# AeroQuad_v300.net
KiCad netlist of a schematic drawn in EAGLE
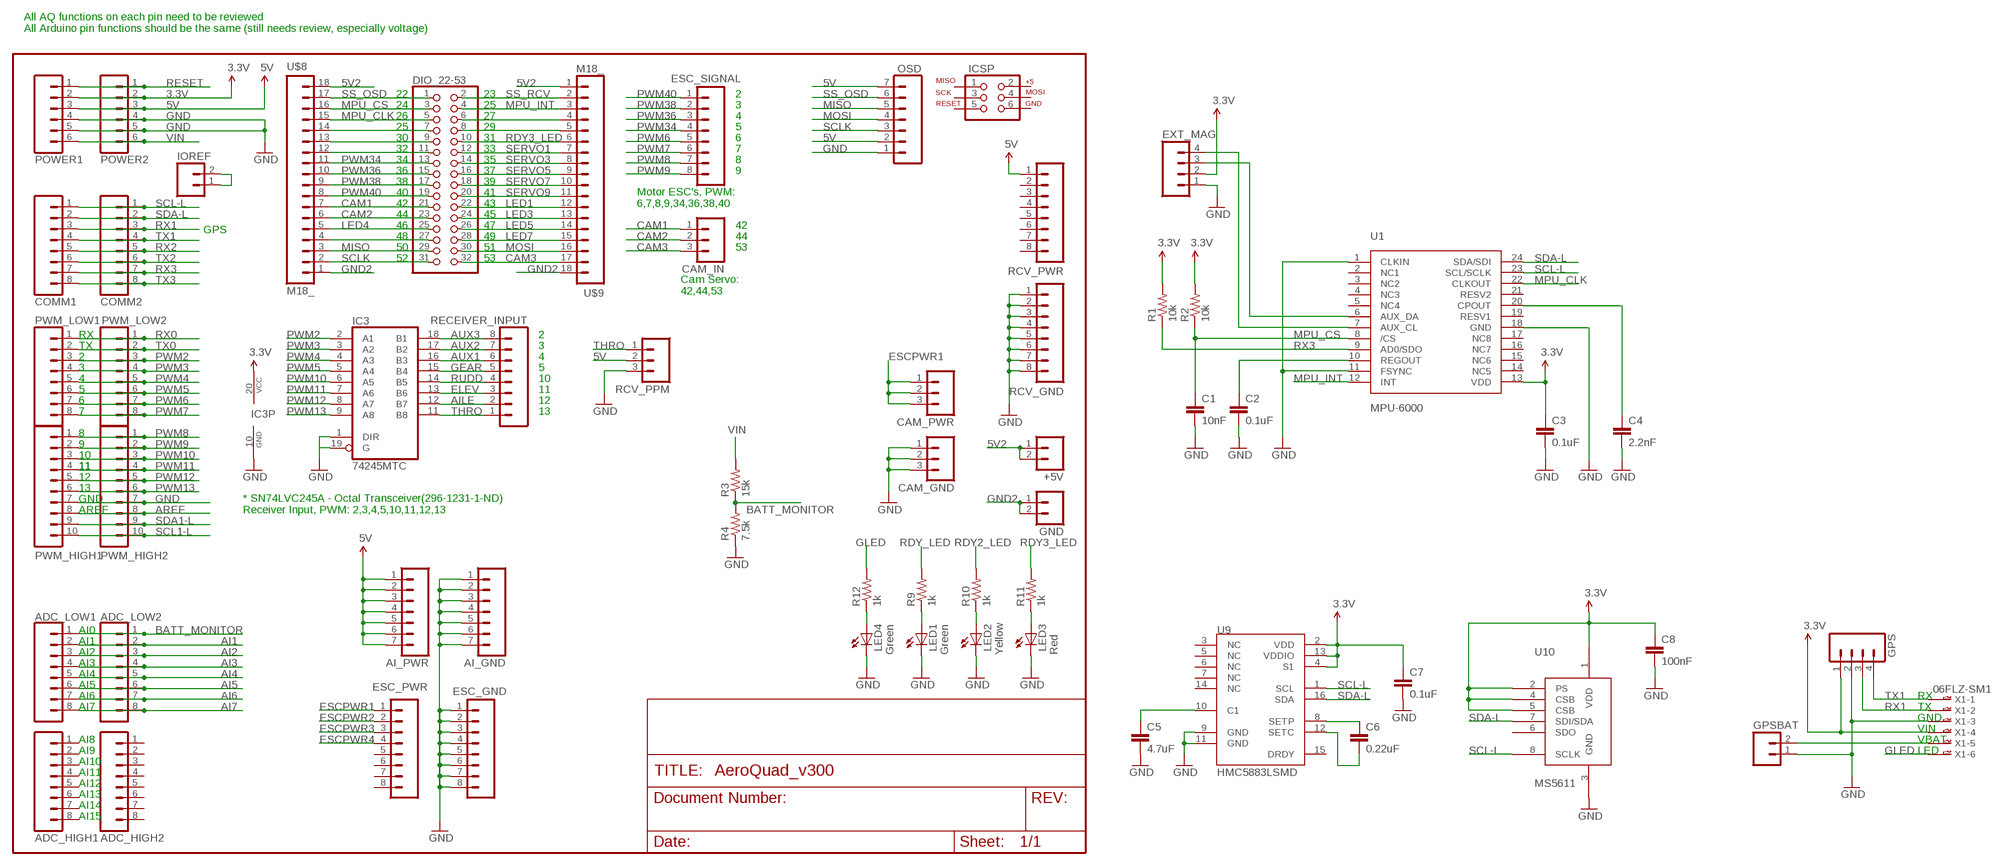
[diagram p0: schematic, sheet 1]

(export (version "E")
  (design (tool "Eeschema 10.0.6"))
  (components
    (comp (ref "+5V")
      (value "M02PTH")
      (footprint "eagle-import:1X02")
      (libsource (lib "eagle-import") (part "M02PTH"))
    )
    (comp (ref "ADC_HIGH1")
      (value "M08LOCK")
      (footprint "eagle-import:1X08_LOCK")
      (libsource (lib "eagle-import") (part "M08LOCK"))
    )
    (comp (ref "ADC_HIGH2")
      (value "M08LOCK")
      (footprint "eagle-import:1X08_LOCK")
      (libsource (lib "eagle-import") (part "M08LOCK"))
    )
    (comp (ref "ADC_LOW1")
      (value "M08LOCK")
      (footprint "eagle-import:1X08_LOCK")
      (libsource (lib "eagle-import") (part "M08LOCK"))
    )
    (comp (ref "ADC_LOW2")
      (value "M08LOCK")
      (footprint "eagle-import:1X08_LOCK")
      (libsource (lib "eagle-import") (part "M08LOCK"))
    )
    (comp (ref "AI_GND")
      (value "M07")
      (footprint "eagle-import:1X07")
      (libsource (lib "eagle-import") (part "M07"))
    )
    (comp (ref "AI_PWR")
      (value "M07")
      (footprint "eagle-import:1X07")
      (libsource (lib "eagle-import") (part "M07"))
    )
    (comp (ref "C1")
      (value "10nF")
      (footprint "eagle-import:0402-CAP")
      (libsource (lib "eagle-import") (part "CAP0402-CAP"))
    )
    (comp (ref "C2")
      (value "0.1uF")
      (footprint "eagle-import:0402-CAP")
      (libsource (lib "eagle-import") (part "CAP0402-CAP"))
    )
    (comp (ref "C3")
      (value "0.1uF")
      (footprint "eagle-import:0402-CAP")
      (libsource (lib "eagle-import") (part "CAP0402-CAP"))
    )
    (comp (ref "C4")
      (value "2.2nF")
      (footprint "eagle-import:0402-CAP")
      (libsource (lib "eagle-import") (part "CAP0402-CAP"))
    )
    (comp (ref "C5")
      (value "4.7uF")
      (footprint "eagle-import:0402-CAP")
      (libsource (lib "eagle-import") (part "CAP0402-CAP"))
    )
    (comp (ref "C6")
      (value "0.22uF")
      (footprint "eagle-import:0402-CAP")
      (libsource (lib "eagle-import") (part "CAP0402-CAP"))
    )
    (comp (ref "C7")
      (value "0.1uF")
      (footprint "eagle-import:0402-CAP")
      (libsource (lib "eagle-import") (part "CAP0402-CAP"))
    )
    (comp (ref "C8")
      (value "100nF")
      (footprint "eagle-import:0402-CAP")
      (libsource (lib "eagle-import") (part "CAP0402-CAP"))
    )
    (comp (ref "CAM_GND")
      (value "M03LOCK")
      (footprint "eagle-import:1X03_LOCK")
      (libsource (lib "eagle-import") (part "M03LOCK"))
    )
    (comp (ref "CAM_IN")
      (value "M03LOCK")
      (footprint "eagle-import:1X03_LOCK")
      (libsource (lib "eagle-import") (part "M03LOCK"))
    )
    (comp (ref "CAM_PWR")
      (value "M03LOCK")
      (footprint "eagle-import:1X03_LOCK")
      (libsource (lib "eagle-import") (part "M03LOCK"))
    )
    (comp (ref "COMM1")
      (value "M08LOCK")
      (footprint "eagle-import:1X08_LOCK")
      (libsource (lib "eagle-import") (part "M08LOCK"))
    )
    (comp (ref "COMM2")
      (value "M08LOCK")
      (footprint "eagle-import:1X08_LOCK")
      (libsource (lib "eagle-import") (part "M08LOCK"))
    )
    (comp (ref "DIO_22-53")
      (value "PINHD-2X16")
      (footprint "eagle-import:2X16")
      (libsource (lib "eagle-import") (part "PINHD-2X16"))
    )
    (comp (ref "ESC_GND")
      (value "M11LOCK")
      (footprint "eagle-import:1X08_LOCK")
      (libsource (lib "eagle-import") (part "M08LOCK"))
    )
    (comp (ref "ESC_PWR")
      (value "M11LOCK")
      (footprint "eagle-import:1X08_LOCK")
      (libsource (lib "eagle-import") (part "M08LOCK"))
    )
    (comp (ref "ESC_SIGNAL")
      (value "M11LOCK")
      (footprint "eagle-import:1X08_LOCK")
      (libsource (lib "eagle-import") (part "M08LOCK"))
    )
    (comp (ref "EXT_MAG")
      (value "M04LOCK")
      (footprint "eagle-import:1X04_LOCK")
      (libsource (lib "eagle-import") (part "M04LOCK"))
    )
    (comp (ref "GND")
      (value "M02PTH")
      (footprint "eagle-import:1X02")
      (libsource (lib "eagle-import") (part "M02PTH"))
    )
    (comp (ref "GPS")
      (value "M04LOCK")
      (footprint "eagle-import:1X04_LOCK")
      (libsource (lib "eagle-import") (part "M04LOCK"))
    )
    (comp (ref "GPSBAT")
      (value "M02PTH")
      (footprint "eagle-import:1X02")
      (libsource (lib "eagle-import") (part "M02PTH"))
    )
    (comp (ref "IC3")
      (value "74245MTC")
      (footprint "eagle-import:SSOP20")
      (libsource (lib "eagle-import") (part "74245MTC"))
    )
    (comp (ref "ICSP")
      (value "AVR_SPI_PRG_6NS")
      (footprint "eagle-import:2X3-NS")
      (libsource (lib "eagle-import") (part "AVR_SPI_PRG_6NS"))
    )
    (comp (ref "IOREF")
      (value "M02LOCK")
      (footprint "eagle-import:1X02_LOCK")
      (libsource (lib "eagle-import") (part "M02LOCK"))
    )
    (comp (ref "LED1")
      (value "Green")
      (footprint "eagle-import:LED-0603")
      (libsource (lib "eagle-import") (part "LED0603"))
    )
    (comp (ref "LED2")
      (value "Yellow")
      (footprint "eagle-import:LED-0603")
      (libsource (lib "eagle-import") (part "LED0603"))
    )
    (comp (ref "LED3")
      (value "Red")
      (footprint "eagle-import:LED-0603")
      (libsource (lib "eagle-import") (part "LED0603"))
    )
    (comp (ref "LED4")
      (value "Green")
      (footprint "eagle-import:LED-0603")
      (libsource (lib "eagle-import") (part "LED0603"))
    )
    (comp (ref "OSD")
      (value "M07LOCK")
      (footprint "eagle-import:1X07_LOCK")
      (libsource (lib "eagle-import") (part "M07LOCK"))
    )
    (comp (ref "POWER1")
      (value "M06LOCK")
      (footprint "eagle-import:1X06_LOCK")
      (libsource (lib "eagle-import") (part "M06LOCK"))
    )
    (comp (ref "POWER2")
      (value "M06LOCK")
      (footprint "eagle-import:1X06_LOCK")
      (libsource (lib "eagle-import") (part "M06LOCK"))
    )
    (comp (ref "PWM_HIGH1")
      (value "M10LOCK")
      (footprint "eagle-import:1X10_LOCK")
      (libsource (lib "eagle-import") (part "M10LOCK"))
    )
    (comp (ref "PWM_HIGH2")
      (value "M10LOCK")
      (footprint "eagle-import:1X10_LOCK")
      (libsource (lib "eagle-import") (part "M10LOCK"))
    )
    (comp (ref "PWM_LOW1")
      (value "M08LOCK")
      (footprint "eagle-import:1X08_LOCK")
      (libsource (lib "eagle-import") (part "M08LOCK"))
    )
    (comp (ref "PWM_LOW2")
      (value "M08LOCK")
      (footprint "eagle-import:1X08_LOCK")
      (libsource (lib "eagle-import") (part "M08LOCK"))
    )
    (comp (ref "R1")
      (value "10k")
      (footprint "eagle-import:0402-RES")
      (libsource (lib "eagle-import") (part "RESISTOR0402-RES"))
    )
    (comp (ref "R2")
      (value "10k")
      (footprint "eagle-import:0402-RES")
      (libsource (lib "eagle-import") (part "RESISTOR0402-RES"))
    )
    (comp (ref "R3")
      (value "15k")
      (footprint "eagle-import:0402-RES")
      (libsource (lib "eagle-import") (part "RESISTOR0402-RES"))
    )
    (comp (ref "R4")
      (value "7.5k")
      (footprint "eagle-import:0402-RES")
      (libsource (lib "eagle-import") (part "RESISTOR0402-RES"))
    )
    (comp (ref "R9")
      (value "1k")
      (footprint "eagle-import:0402-RES")
      (libsource (lib "eagle-import") (part "RESISTOR0402-RES"))
    )
    (comp (ref "R10")
      (value "1k")
      (footprint "eagle-import:0402-RES")
      (libsource (lib "eagle-import") (part "RESISTOR0402-RES"))
    )
    (comp (ref "R11")
      (value "1k")
      (footprint "eagle-import:0402-RES")
      (libsource (lib "eagle-import") (part "RESISTOR0402-RES"))
    )
    (comp (ref "R12")
      (value "1k")
      (footprint "eagle-import:0402-RES")
      (libsource (lib "eagle-import") (part "RESISTOR0402-RES"))
    )
    (comp (ref "RCV_GND")
      (value "M10LOCK")
      (footprint "eagle-import:1X08_LOCK")
      (libsource (lib "eagle-import") (part "M08LOCK"))
    )
    (comp (ref "RCV_PPM")
      (value "M03LOCK")
      (footprint "eagle-import:1X03_LOCK")
      (libsource (lib "eagle-import") (part "M03LOCK"))
    )
    (comp (ref "RCV_PWR")
      (value "M10LOCK")
      (footprint "eagle-import:1X08_LOCK")
      (libsource (lib "eagle-import") (part "M08LOCK"))
    )
    (comp (ref "RECEIVER_INPUT")
      (value "M08LOCK")
      (footprint "eagle-import:1X08_LOCK")
      (libsource (lib "eagle-import") (part "M08LOCK"))
    )
    (comp (ref "U$8")
      (value "M18_")
      (footprint "eagle-import:1X18")
      (libsource (lib "eagle-import") (part "M18_"))
    )
    (comp (ref "U$9")
      (value "M18_")
      (footprint "eagle-import:1X18")
      (libsource (lib "eagle-import") (part "M18_"))
    )
    (comp (ref "U1")
      (value "MPU-6000")
      (footprint "eagle-import:QFN-24")
      (libsource (lib "eagle-import") (part "MPU-6000"))
    )
    (comp (ref "U9")
      (value "HMC5883LSMD")
      (footprint "eagle-import:16LPCC")
      (libsource (lib "eagle-import") (part "HMC5883LSMD"))
    )
    (comp (ref "U10")
      (value "MS5611")
      (footprint "eagle-import:LGA08A")
      (libsource (lib "eagle-import") (part "MS5611"))
    )
    (comp (ref "X1")
      (value "06FLZ-SM1")
      (footprint "eagle-import:6FLZ-SM")
      (libsource (lib "eagle-import") (part "06FLZ-SM1"))
    )
  )
  (nets
    (net (code "1") (name "/5V2") (class "Default")
      (node (ref "+5V") (pin "1") (pinfunction "1_1") (pintype "passive"))
      (node (ref "+5V") (pin "2") (pinfunction "2_2") (pintype "passive"))
      (node (ref "U$8") (pin "18") (pinfunction "18_18") (pintype "passive"))
      (node (ref "U$9") (pin "1") (pinfunction "1_1") (pintype "passive"))
    )
    (net (code "2") (name "/AI1") (class "Default")
      (node (ref "ADC_LOW1") (pin "2") (pinfunction "2_2") (pintype "passive"))
      (node (ref "ADC_LOW2") (pin "2") (pinfunction "2_2") (pintype "passive"))
    )
    (net (code "3") (name "/AI2") (class "Default")
      (node (ref "ADC_LOW1") (pin "3") (pinfunction "3_3") (pintype "passive"))
      (node (ref "ADC_LOW2") (pin "3") (pinfunction "3_3") (pintype "passive"))
    )
    (net (code "4") (name "/AI3") (class "Default")
      (node (ref "ADC_LOW1") (pin "4") (pinfunction "4_4") (pintype "passive"))
      (node (ref "ADC_LOW2") (pin "4") (pinfunction "4_4") (pintype "passive"))
    )
    (net (code "5") (name "/AI4") (class "Default")
      (node (ref "ADC_LOW1") (pin "5") (pinfunction "5_5") (pintype "passive"))
      (node (ref "ADC_LOW2") (pin "5") (pinfunction "5_5") (pintype "passive"))
    )
    (net (code "6") (name "/AI5") (class "Default")
      (node (ref "ADC_LOW1") (pin "6") (pinfunction "6_6") (pintype "passive"))
      (node (ref "ADC_LOW2") (pin "6") (pinfunction "6_6") (pintype "passive"))
    )
    (net (code "7") (name "/AI6") (class "Default")
      (node (ref "ADC_LOW1") (pin "7") (pinfunction "7_7") (pintype "passive"))
      (node (ref "ADC_LOW2") (pin "7") (pinfunction "7_7") (pintype "passive"))
    )
    (net (code "8") (name "/AI7") (class "Default")
      (node (ref "ADC_LOW1") (pin "8") (pinfunction "8_8") (pintype "passive"))
      (node (ref "ADC_LOW2") (pin "8") (pinfunction "8_8") (pintype "passive"))
    )
    (net (code "9") (name "/AILE") (class "Default")
      (node (ref "IC3") (pin "12") (pinfunction "B7_12") (pintype "bidirectional"))
      (node (ref "RECEIVER_INPUT") (pin "2") (pinfunction "2_2") (pintype "passive"))
    )
    (net (code "10") (name "/AREF") (class "Default")
      (node (ref "PWM_HIGH1") (pin "8") (pinfunction "8_8") (pintype "passive"))
      (node (ref "PWM_HIGH2") (pin "8") (pinfunction "8_8") (pintype "passive"))
    )
    (net (code "11") (name "/AUX1") (class "Default")
      (node (ref "IC3") (pin "16") (pinfunction "B3_16") (pintype "bidirectional"))
      (node (ref "RECEIVER_INPUT") (pin "6") (pinfunction "6_6") (pintype "passive"))
    )
    (net (code "12") (name "/AUX2") (class "Default")
      (node (ref "IC3") (pin "17") (pinfunction "B2_17") (pintype "bidirectional"))
      (node (ref "RECEIVER_INPUT") (pin "7") (pinfunction "7_7") (pintype "passive"))
    )
    (net (code "13") (name "/AUX3") (class "Default")
      (node (ref "IC3") (pin "18") (pinfunction "B1_18") (pintype "bidirectional"))
      (node (ref "RECEIVER_INPUT") (pin "8") (pinfunction "8_8") (pintype "passive"))
    )
    (net (code "14") (name "/BATT_MONITOR") (class "Default")
      (node (ref "ADC_LOW1") (pin "1") (pinfunction "1_1") (pintype "passive"))
      (node (ref "ADC_LOW2") (pin "1") (pinfunction "1_1") (pintype "passive"))
      (node (ref "R3") (pin "1") (pinfunction "1_1") (pintype "passive"))
      (node (ref "R4") (pin "2") (pinfunction "2_2") (pintype "passive"))
    )
    (net (code "15") (name "/CAM1") (class "Default")
      (node (ref "CAM_IN") (pin "1") (pinfunction "1_1") (pintype "passive"))
      (node (ref "DIO_22-53") (pin "21") (pinfunction "21_21") (pintype "passive"))
      (node (ref "U$8") (pin "7") (pinfunction "7_7") (pintype "passive"))
    )
    (net (code "16") (name "/CAM2") (class "Default")
      (node (ref "CAM_IN") (pin "2") (pinfunction "2_2") (pintype "passive"))
      (node (ref "DIO_22-53") (pin "23") (pinfunction "23_23") (pintype "passive"))
      (node (ref "U$8") (pin "6") (pinfunction "6_6") (pintype "passive"))
    )
    (net (code "17") (name "/CAM3") (class "Default")
      (node (ref "CAM_IN") (pin "3") (pinfunction "3_3") (pintype "passive"))
      (node (ref "DIO_22-53") (pin "32") (pinfunction "32_32") (pintype "passive"))
      (node (ref "U$9") (pin "17") (pinfunction "17_17") (pintype "passive"))
    )
    (net (code "18") (name "/ELEV") (class "Default")
      (node (ref "IC3") (pin "13") (pinfunction "B6_13") (pintype "bidirectional"))
      (node (ref "RECEIVER_INPUT") (pin "3") (pinfunction "3_3") (pintype "passive"))
    )
    (net (code "19") (name "/ESCPWR1") (class "Default")
      (node (ref "CAM_PWR") (pin "1") (pinfunction "1_1") (pintype "passive"))
      (node (ref "CAM_PWR") (pin "2") (pinfunction "2_2") (pintype "passive"))
      (node (ref "CAM_PWR") (pin "3") (pinfunction "3_3") (pintype "passive"))
      (node (ref "ESC_PWR") (pin "1") (pinfunction "1_1") (pintype "passive"))
    )
    (net (code "20") (name "/ESCPWR2") (class "Default")
      (node (ref "ESC_PWR") (pin "2") (pinfunction "2_2") (pintype "passive"))
    )
    (net (code "21") (name "/ESCPWR3") (class "Default")
      (node (ref "ESC_PWR") (pin "3") (pinfunction "3_3") (pintype "passive"))
    )
    (net (code "22") (name "/ESCPWR4") (class "Default")
      (node (ref "ESC_PWR") (pin "4") (pinfunction "4_4") (pintype "passive"))
    )
    (net (code "23") (name "/GEAR") (class "Default")
      (node (ref "IC3") (pin "15") (pinfunction "B4_15") (pintype "bidirectional"))
      (node (ref "RECEIVER_INPUT") (pin "5") (pinfunction "5_5") (pintype "passive"))
    )
    (net (code "24") (name "/GLED") (class "Default")
      (node (ref "R12") (pin "2") (pinfunction "2_2") (pintype "passive"))
      (node (ref "X1") (pin "6") (pinfunction "1_6") (pintype "passive"))
    )
    (net (code "25") (name "/GND2") (class "Default")
      (node (ref "GND") (pin "1") (pinfunction "1_1") (pintype "passive"))
      (node (ref "GND") (pin "2") (pinfunction "2_2") (pintype "passive"))
      (node (ref "U$8") (pin "1") (pinfunction "1_1") (pintype "passive"))
      (node (ref "U$9") (pin "18") (pinfunction "18_18") (pintype "passive"))
    )
    (net (code "26") (name "/LED1") (class "Default")
      (node (ref "DIO_22-53") (pin "22") (pinfunction "22_22") (pintype "passive"))
      (node (ref "U$9") (pin "12") (pinfunction "12_12") (pintype "passive"))
    )
    (net (code "27") (name "/LED3") (class "Default")
      (node (ref "DIO_22-53") (pin "24") (pinfunction "24_24") (pintype "passive"))
      (node (ref "U$9") (pin "13") (pinfunction "13_13") (pintype "passive"))
    )
    (net (code "28") (name "/LED4") (class "Default")
      (node (ref "DIO_22-53") (pin "25") (pinfunction "25_25") (pintype "passive"))
      (node (ref "U$8") (pin "5") (pinfunction "5_5") (pintype "passive"))
    )
    (net (code "29") (name "/LED5") (class "Default")
      (node (ref "DIO_22-53") (pin "26") (pinfunction "26_26") (pintype "passive"))
      (node (ref "U$9") (pin "14") (pinfunction "14_14") (pintype "passive"))
    )
    (net (code "30") (name "/LED7") (class "Default")
      (node (ref "DIO_22-53") (pin "28") (pinfunction "28_28") (pintype "passive"))
      (node (ref "U$9") (pin "15") (pinfunction "15_15") (pintype "passive"))
    )
    (net (code "31") (name "/MISO") (class "Default")
      (node (ref "DIO_22-53") (pin "29") (pinfunction "29_29") (pintype "passive"))
      (node (ref "OSD") (pin "5") (pinfunction "5_5") (pintype "passive"))
      (node (ref "U$8") (pin "3") (pinfunction "3_3") (pintype "passive"))
    )
    (net (code "32") (name "/MOSI") (class "Default")
      (node (ref "DIO_22-53") (pin "30") (pinfunction "30_30") (pintype "passive"))
      (node (ref "OSD") (pin "4") (pinfunction "4_4") (pintype "passive"))
      (node (ref "U$9") (pin "16") (pinfunction "16_16") (pintype "passive"))
    )
    (net (code "33") (name "/MPU_CLK") (class "Default")
      (node (ref "DIO_22-53") (pin "5") (pinfunction "5_5") (pintype "passive"))
      (node (ref "U$8") (pin "15") (pinfunction "15_15") (pintype "passive"))
      (node (ref "U1") (pin "22") (pinfunction "CLKOUT_22") (pintype "bidirectional"))
    )
    (net (code "34") (name "/MPU_CS") (class "Default")
      (node (ref "C1") (pin "1") (pinfunction "1_1") (pintype "passive"))
      (node (ref "DIO_22-53") (pin "3") (pinfunction "3_3") (pintype "passive"))
      (node (ref "R2") (pin "1") (pinfunction "1_1") (pintype "passive"))
      (node (ref "U$8") (pin "16") (pinfunction "16_16") (pintype "passive"))
      (node (ref "U1") (pin "8") (pinfunction "/CS_8") (pintype "bidirectional"))
    )
    (net (code "35") (name "/MPU_INT") (class "Default")
      (node (ref "DIO_22-53") (pin "4") (pinfunction "4_4") (pintype "passive"))
      (node (ref "U$9") (pin "3") (pinfunction "3_3") (pintype "passive"))
      (node (ref "U1") (pin "12") (pinfunction "INT_12") (pintype "bidirectional"))
    )
    (net (code "36") (name "/PWM2") (class "Default")
      (node (ref "IC3") (pin "2") (pinfunction "A1_2") (pintype "bidirectional"))
      (node (ref "PWM_LOW1") (pin "3") (pinfunction "3_3") (pintype "passive"))
      (node (ref "PWM_LOW2") (pin "3") (pinfunction "3_3") (pintype "passive"))
    )
    (net (code "37") (name "/PWM3") (class "Default")
      (node (ref "IC3") (pin "3") (pinfunction "A2_3") (pintype "bidirectional"))
      (node (ref "PWM_LOW1") (pin "4") (pinfunction "4_4") (pintype "passive"))
      (node (ref "PWM_LOW2") (pin "4") (pinfunction "4_4") (pintype "passive"))
    )
    (net (code "38") (name "/PWM4") (class "Default")
      (node (ref "IC3") (pin "4") (pinfunction "A3_4") (pintype "bidirectional"))
      (node (ref "PWM_LOW1") (pin "5") (pinfunction "5_5") (pintype "passive"))
      (node (ref "PWM_LOW2") (pin "5") (pinfunction "5_5") (pintype "passive"))
    )
    (net (code "39") (name "/PWM5") (class "Default")
      (node (ref "IC3") (pin "5") (pinfunction "A4_5") (pintype "bidirectional"))
      (node (ref "PWM_LOW1") (pin "6") (pinfunction "6_6") (pintype "passive"))
      (node (ref "PWM_LOW2") (pin "6") (pinfunction "6_6") (pintype "passive"))
    )
    (net (code "40") (name "/PWM6") (class "Default")
      (node (ref "ESC_SIGNAL") (pin "5") (pinfunction "5_5") (pintype "passive"))
      (node (ref "PWM_LOW1") (pin "7") (pinfunction "7_7") (pintype "passive"))
      (node (ref "PWM_LOW2") (pin "7") (pinfunction "7_7") (pintype "passive"))
    )
    (net (code "41") (name "/PWM7") (class "Default")
      (node (ref "ESC_SIGNAL") (pin "6") (pinfunction "6_6") (pintype "passive"))
      (node (ref "PWM_LOW1") (pin "8") (pinfunction "8_8") (pintype "passive"))
      (node (ref "PWM_LOW2") (pin "8") (pinfunction "8_8") (pintype "passive"))
    )
    (net (code "42") (name "/PWM8") (class "Default")
      (node (ref "ESC_SIGNAL") (pin "7") (pinfunction "7_7") (pintype "passive"))
      (node (ref "PWM_HIGH1") (pin "1") (pinfunction "1_1") (pintype "passive"))
      (node (ref "PWM_HIGH2") (pin "1") (pinfunction "1_1") (pintype "passive"))
    )
    (net (code "43") (name "/PWM9") (class "Default")
      (node (ref "ESC_SIGNAL") (pin "8") (pinfunction "8_8") (pintype "passive"))
      (node (ref "PWM_HIGH1") (pin "2") (pinfunction "2_2") (pintype "passive"))
      (node (ref "PWM_HIGH2") (pin "2") (pinfunction "2_2") (pintype "passive"))
    )
    (net (code "44") (name "/PWM10") (class "Default")
      (node (ref "IC3") (pin "6") (pinfunction "A5_6") (pintype "bidirectional"))
      (node (ref "PWM_HIGH1") (pin "3") (pinfunction "3_3") (pintype "passive"))
      (node (ref "PWM_HIGH2") (pin "3") (pinfunction "3_3") (pintype "passive"))
    )
    (net (code "45") (name "/PWM11") (class "Default")
      (node (ref "IC3") (pin "7") (pinfunction "A6_7") (pintype "bidirectional"))
      (node (ref "PWM_HIGH1") (pin "4") (pinfunction "4_4") (pintype "passive"))
      (node (ref "PWM_HIGH2") (pin "4") (pinfunction "4_4") (pintype "passive"))
    )
    (net (code "46") (name "/PWM12") (class "Default")
      (node (ref "IC3") (pin "8") (pinfunction "A7_8") (pintype "bidirectional"))
      (node (ref "PWM_HIGH1") (pin "5") (pinfunction "5_5") (pintype "passive"))
      (node (ref "PWM_HIGH2") (pin "5") (pinfunction "5_5") (pintype "passive"))
    )
    (net (code "47") (name "/PWM13") (class "Default")
      (node (ref "IC3") (pin "9") (pinfunction "A8_9") (pintype "bidirectional"))
      (node (ref "PWM_HIGH1") (pin "6") (pinfunction "6_6") (pintype "passive"))
      (node (ref "PWM_HIGH2") (pin "6") (pinfunction "6_6") (pintype "passive"))
    )
    (net (code "48") (name "/PWM34") (class "Default")
      (node (ref "DIO_22-53") (pin "13") (pinfunction "13_13") (pintype "passive"))
      (node (ref "ESC_SIGNAL") (pin "4") (pinfunction "4_4") (pintype "passive"))
      (node (ref "U$8") (pin "11") (pinfunction "11_11") (pintype "passive"))
    )
    (net (code "49") (name "/PWM36") (class "Default")
      (node (ref "DIO_22-53") (pin "15") (pinfunction "15_15") (pintype "passive"))
      (node (ref "ESC_SIGNAL") (pin "3") (pinfunction "3_3") (pintype "passive"))
      (node (ref "U$8") (pin "10") (pinfunction "10_10") (pintype "passive"))
    )
    (net (code "50") (name "/PWM38") (class "Default")
      (node (ref "DIO_22-53") (pin "17") (pinfunction "17_17") (pintype "passive"))
      (node (ref "ESC_SIGNAL") (pin "2") (pinfunction "2_2") (pintype "passive"))
      (node (ref "U$8") (pin "9") (pinfunction "9_9") (pintype "passive"))
    )
    (net (code "51") (name "/PWM40") (class "Default")
      (node (ref "DIO_22-53") (pin "19") (pinfunction "19_19") (pintype "passive"))
      (node (ref "ESC_SIGNAL") (pin "1") (pinfunction "1_1") (pintype "passive"))
      (node (ref "U$8") (pin "8") (pinfunction "8_8") (pintype "passive"))
    )
    (net (code "52") (name "/RDY2_LED") (class "Default")
      (node (ref "R10") (pin "2") (pinfunction "2_2") (pintype "passive"))
    )
    (net (code "53") (name "/RDY3_LED") (class "Default")
      (node (ref "DIO_22-53") (pin "10") (pinfunction "10_10") (pintype "passive"))
      (node (ref "R11") (pin "2") (pinfunction "2_2") (pintype "passive"))
      (node (ref "U$9") (pin "6") (pinfunction "6_6") (pintype "passive"))
    )
    (net (code "54") (name "/RDY_LED") (class "Default")
      (node (ref "R9") (pin "2") (pinfunction "2_2") (pintype "passive"))
    )
    (net (code "55") (name "/RESET") (class "Default")
      (node (ref "POWER1") (pin "1") (pinfunction "1_1") (pintype "passive"))
      (node (ref "POWER2") (pin "1") (pinfunction "1_1") (pintype "passive"))
    )
    (net (code "56") (name "/RUDD") (class "Default")
      (node (ref "IC3") (pin "14") (pinfunction "B5_14") (pintype "bidirectional"))
      (node (ref "RECEIVER_INPUT") (pin "4") (pinfunction "4_4") (pintype "passive"))
    )
    (net (code "57") (name "/RX0") (class "Default")
      (node (ref "PWM_LOW1") (pin "1") (pinfunction "1_1") (pintype "passive"))
      (node (ref "PWM_LOW2") (pin "1") (pinfunction "1_1") (pintype "passive"))
    )
    (net (code "58") (name "/RX1") (class "Default")
      (node (ref "COMM1") (pin "3") (pinfunction "3_3") (pintype "passive"))
      (node (ref "COMM2") (pin "3") (pinfunction "3_3") (pintype "passive"))
      (node (ref "GPS") (pin "3") (pinfunction "3_3") (pintype "passive"))
      (node (ref "X1") (pin "2") (pinfunction "1_2") (pintype "passive"))
    )
    (net (code "59") (name "/RX2") (class "Default")
      (node (ref "COMM1") (pin "5") (pinfunction "5_5") (pintype "passive"))
      (node (ref "COMM2") (pin "5") (pinfunction "5_5") (pintype "passive"))
    )
    (net (code "60") (name "/RX3") (class "Default")
      (node (ref "COMM1") (pin "7") (pinfunction "7_7") (pintype "passive"))
      (node (ref "COMM2") (pin "7") (pinfunction "7_7") (pintype "passive"))
      (node (ref "R1") (pin "1") (pinfunction "1_1") (pintype "passive"))
      (node (ref "U1") (pin "9") (pinfunction "AD0/SDO_9") (pintype "bidirectional"))
    )
    (net (code "61") (name "/SCL-L") (class "Default")
      (node (ref "COMM1") (pin "1") (pinfunction "1_1") (pintype "passive"))
      (node (ref "COMM2") (pin "1") (pinfunction "1_1") (pintype "passive"))
      (node (ref "U1") (pin "23") (pinfunction "SCL/SCLK_23") (pintype "bidirectional"))
      (node (ref "U10") (pin "8") (pinfunction "SCLK_8") (pintype "bidirectional"))
      (node (ref "U9") (pin "1") (pinfunction "SCL_1") (pintype "bidirectional"))
    )
    (net (code "62") (name "/SCL1-L") (class "Default")
      (node (ref "PWM_HIGH1") (pin "10") (pinfunction "10_10") (pintype "passive"))
      (node (ref "PWM_HIGH2") (pin "10") (pinfunction "10_10") (pintype "passive"))
    )
    (net (code "63") (name "/SCLK") (class "Default")
      (node (ref "DIO_22-53") (pin "31") (pinfunction "31_31") (pintype "passive"))
      (node (ref "OSD") (pin "3") (pinfunction "3_3") (pintype "passive"))
      (node (ref "U$8") (pin "2") (pinfunction "2_2") (pintype "passive"))
    )
    (net (code "64") (name "/SDA-L") (class "Default")
      (node (ref "COMM1") (pin "2") (pinfunction "2_2") (pintype "passive"))
      (node (ref "COMM2") (pin "2") (pinfunction "2_2") (pintype "passive"))
      (node (ref "U1") (pin "24") (pinfunction "SDA/SDI_24") (pintype "bidirectional"))
      (node (ref "U10") (pin "7") (pinfunction "SDI/SDA_7") (pintype "bidirectional"))
      (node (ref "U9") (pin "16") (pinfunction "SDA_16") (pintype "bidirectional"))
    )
    (net (code "65") (name "/SDA1-L") (class "Default")
      (node (ref "PWM_HIGH1") (pin "9") (pinfunction "9_9") (pintype "passive"))
      (node (ref "PWM_HIGH2") (pin "9") (pinfunction "9_9") (pintype "passive"))
    )
    (net (code "66") (name "/SERVO1") (class "Default")
      (node (ref "DIO_22-53") (pin "12") (pinfunction "12_12") (pintype "passive"))
      (node (ref "U$9") (pin "7") (pinfunction "7_7") (pintype "passive"))
    )
    (net (code "67") (name "/SERVO3") (class "Default")
      (node (ref "DIO_22-53") (pin "14") (pinfunction "14_14") (pintype "passive"))
      (node (ref "U$9") (pin "8") (pinfunction "8_8") (pintype "passive"))
    )
    (net (code "68") (name "/SERVO5") (class "Default")
      (node (ref "DIO_22-53") (pin "16") (pinfunction "16_16") (pintype "passive"))
      (node (ref "U$9") (pin "9") (pinfunction "9_9") (pintype "passive"))
    )
    (net (code "69") (name "/SERVO7") (class "Default")
      (node (ref "DIO_22-53") (pin "18") (pinfunction "18_18") (pintype "passive"))
      (node (ref "U$9") (pin "10") (pinfunction "10_10") (pintype "passive"))
    )
    (net (code "70") (name "/SERVO9") (class "Default")
      (node (ref "DIO_22-53") (pin "20") (pinfunction "20_20") (pintype "passive"))
      (node (ref "U$9") (pin "11") (pinfunction "11_11") (pintype "passive"))
    )
    (net (code "71") (name "/SS_OSD") (class "Default")
      (node (ref "DIO_22-53") (pin "1") (pinfunction "1_1") (pintype "passive"))
      (node (ref "OSD") (pin "6") (pinfunction "6_6") (pintype "passive"))
      (node (ref "U$8") (pin "17") (pinfunction "17_17") (pintype "passive"))
    )
    (net (code "72") (name "/SS_RCV") (class "Default")
      (node (ref "DIO_22-53") (pin "2") (pinfunction "2_2") (pintype "passive"))
      (node (ref "U$9") (pin "2") (pinfunction "2_2") (pintype "passive"))
    )
    (net (code "73") (name "/THRO") (class "Default")
      (node (ref "IC3") (pin "11") (pinfunction "B8_11") (pintype "bidirectional"))
      (node (ref "RCV_PPM") (pin "1") (pinfunction "1_1") (pintype "passive"))
      (node (ref "RECEIVER_INPUT") (pin "1") (pinfunction "1_1") (pintype "passive"))
    )
    (net (code "74") (name "/TX0") (class "Default")
      (node (ref "PWM_LOW1") (pin "2") (pinfunction "2_2") (pintype "passive"))
      (node (ref "PWM_LOW2") (pin "2") (pinfunction "2_2") (pintype "passive"))
    )
    (net (code "75") (name "/TX1") (class "Default")
      (node (ref "COMM1") (pin "4") (pinfunction "4_4") (pintype "passive"))
      (node (ref "COMM2") (pin "4") (pinfunction "4_4") (pintype "passive"))
      (node (ref "GPS") (pin "4") (pinfunction "4_4") (pintype "passive"))
      (node (ref "X1") (pin "1") (pinfunction "1_1") (pintype "passive"))
    )
    (net (code "76") (name "/TX2") (class "Default")
      (node (ref "COMM1") (pin "6") (pinfunction "6_6") (pintype "passive"))
      (node (ref "COMM2") (pin "6") (pinfunction "6_6") (pintype "passive"))
    )
    (net (code "77") (name "/TX3") (class "Default")
      (node (ref "COMM1") (pin "8") (pinfunction "8_8") (pintype "passive"))
      (node (ref "COMM2") (pin "8") (pinfunction "8_8") (pintype "passive"))
    )
    (net (code "78") (name "/VIN") (class "Default")
      (node (ref "POWER1") (pin "6") (pinfunction "6_6") (pintype "passive"))
      (node (ref "POWER2") (pin "6") (pinfunction "6_6") (pintype "passive"))
      (node (ref "R3") (pin "2") (pinfunction "2_2") (pintype "passive"))
    )
    (net (code "79") (name "3.3V") (class "Default")
      (node (ref "C3") (pin "1") (pinfunction "1_1") (pintype "passive"))
      (node (ref "C7") (pin "1") (pinfunction "1_1") (pintype "passive"))
      (node (ref "C8") (pin "1") (pinfunction "1_1") (pintype "passive"))
      (node (ref "EXT_MAG") (pin "2") (pinfunction "2_2") (pintype "passive"))
      (node (ref "GPS") (pin "1") (pinfunction "1_1") (pintype "passive"))
      (node (ref "IC3") (pin "20") (pinfunction "VCC_20") (pintype "power_in"))
      (node (ref "POWER1") (pin "2") (pinfunction "2_2") (pintype "passive"))
      (node (ref "POWER2") (pin "2") (pinfunction "2_2") (pintype "passive"))
      (node (ref "R1") (pin "2") (pinfunction "2_2") (pintype "passive"))
      (node (ref "R2") (pin "2") (pinfunction "2_2") (pintype "passive"))
      (node (ref "U1") (pin "13") (pinfunction "VDD_13") (pintype "bidirectional"))
      (node (ref "U10") (pin "1") (pinfunction "VDD_1") (pintype "bidirectional"))
      (node (ref "U10") (pin "2") (pinfunction "PS_2") (pintype "bidirectional"))
      (node (ref "U10") (pin "4") (pinfunction "CSB_4") (pintype "bidirectional"))
      (node (ref "U10") (pin "5") (pinfunction "CSB_5") (pintype "bidirectional"))
      (node (ref "U9") (pin "13") (pinfunction "VDDIO_13") (pintype "bidirectional"))
      (node (ref "U9") (pin "2") (pinfunction "VDD_2") (pintype "bidirectional"))
      (node (ref "U9") (pin "4") (pinfunction "S1_4") (pintype "bidirectional"))
      (node (ref "X1") (pin "4") (pinfunction "1_4") (pintype "passive"))
    )
    (net (code "80") (name "5V") (class "Default")
      (node (ref "AI_PWR") (pin "1") (pinfunction "1_1") (pintype "passive"))
      (node (ref "AI_PWR") (pin "2") (pinfunction "2_2") (pintype "passive"))
      (node (ref "AI_PWR") (pin "3") (pinfunction "3_3") (pintype "passive"))
      (node (ref "AI_PWR") (pin "4") (pinfunction "4_4") (pintype "passive"))
      (node (ref "AI_PWR") (pin "5") (pinfunction "5_5") (pintype "passive"))
      (node (ref "AI_PWR") (pin "6") (pinfunction "6_6") (pintype "passive"))
      (node (ref "AI_PWR") (pin "7") (pinfunction "7_7") (pintype "passive"))
      (node (ref "OSD") (pin "2") (pinfunction "2_2") (pintype "passive"))
      (node (ref "OSD") (pin "7") (pinfunction "7_7") (pintype "passive"))
      (node (ref "POWER1") (pin "3") (pinfunction "3_3") (pintype "passive"))
      (node (ref "POWER2") (pin "3") (pinfunction "3_3") (pintype "passive"))
      (node (ref "RCV_PPM") (pin "2") (pinfunction "2_2") (pintype "passive"))
      (node (ref "RCV_PWR") (pin "1") (pinfunction "1_1") (pintype "passive"))
    )
    (net (code "81") (name "GND") (class "Default")
      (node (ref "AI_GND") (pin "1") (pinfunction "1_1") (pintype "passive"))
      (node (ref "AI_GND") (pin "2") (pinfunction "2_2") (pintype "passive"))
      (node (ref "AI_GND") (pin "3") (pinfunction "3_3") (pintype "passive"))
      (node (ref "AI_GND") (pin "4") (pinfunction "4_4") (pintype "passive"))
      (node (ref "AI_GND") (pin "5") (pinfunction "5_5") (pintype "passive"))
      (node (ref "AI_GND") (pin "6") (pinfunction "6_6") (pintype "passive"))
      (node (ref "AI_GND") (pin "7") (pinfunction "7_7") (pintype "passive"))
      (node (ref "C1") (pin "2") (pinfunction "2_2") (pintype "passive"))
      (node (ref "C2") (pin "2") (pinfunction "2_2") (pintype "passive"))
      (node (ref "C3") (pin "2") (pinfunction "2_2") (pintype "passive"))
      (node (ref "C4") (pin "2") (pinfunction "2_2") (pintype "passive"))
      (node (ref "C5") (pin "2") (pinfunction "2_2") (pintype "passive"))
      (node (ref "C7") (pin "2") (pinfunction "2_2") (pintype "passive"))
      (node (ref "C8") (pin "2") (pinfunction "2_2") (pintype "passive"))
      (node (ref "CAM_GND") (pin "1") (pinfunction "1_1") (pintype "passive"))
      (node (ref "CAM_GND") (pin "2") (pinfunction "2_2") (pintype "passive"))
      (node (ref "CAM_GND") (pin "3") (pinfunction "3_3") (pintype "passive"))
      (node (ref "ESC_GND") (pin "1") (pinfunction "1_1") (pintype "passive"))
      (node (ref "ESC_GND") (pin "2") (pinfunction "2_2") (pintype "passive"))
      (node (ref "ESC_GND") (pin "3") (pinfunction "3_3") (pintype "passive"))
      (node (ref "ESC_GND") (pin "4") (pinfunction "4_4") (pintype "passive"))
      (node (ref "ESC_GND") (pin "5") (pinfunction "5_5") (pintype "passive"))
      (node (ref "ESC_GND") (pin "6") (pinfunction "6_6") (pintype "passive"))
      (node (ref "ESC_GND") (pin "7") (pinfunction "7_7") (pintype "passive"))
      (node (ref "ESC_GND") (pin "8") (pinfunction "8_8") (pintype "passive"))
      (node (ref "EXT_MAG") (pin "1") (pinfunction "1_1") (pintype "passive"))
      (node (ref "GPS") (pin "2") (pinfunction "2_2") (pintype "passive"))
      (node (ref "GPSBAT") (pin "1") (pinfunction "1_1") (pintype "passive"))
      (node (ref "IC3") (pin "1") (pinfunction "DIR_1") (pintype "input"))
      (node (ref "IC3") (pin "10") (pinfunction "GND_10") (pintype "power_in"))
      (node (ref "IC3") (pin "19") (pinfunction "G_19") (pintype "input"))
      (node (ref "LED1") (pin "C") (pinfunction "C_C") (pintype "passive"))
      (node (ref "LED2") (pin "C") (pinfunction "C_C") (pintype "passive"))
      (node (ref "LED3") (pin "C") (pinfunction "C_C") (pintype "passive"))
      (node (ref "LED4") (pin "C") (pinfunction "C_C") (pintype "passive"))
      (node (ref "OSD") (pin "1") (pinfunction "1_1") (pintype "passive"))
      (node (ref "POWER1") (pin "4") (pinfunction "4_4") (pintype "passive"))
      (node (ref "POWER1") (pin "5") (pinfunction "5_5") (pintype "passive"))
      (node (ref "POWER2") (pin "4") (pinfunction "4_4") (pintype "passive"))
      (node (ref "POWER2") (pin "5") (pinfunction "5_5") (pintype "passive"))
      (node (ref "PWM_HIGH1") (pin "7") (pinfunction "7_7") (pintype "passive"))
      (node (ref "PWM_HIGH2") (pin "7") (pinfunction "7_7") (pintype "passive"))
      (node (ref "R4") (pin "1") (pinfunction "1_1") (pintype "passive"))
      (node (ref "RCV_GND") (pin "1") (pinfunction "1_1") (pintype "passive"))
      (node (ref "RCV_GND") (pin "2") (pinfunction "2_2") (pintype "passive"))
      (node (ref "RCV_GND") (pin "3") (pinfunction "3_3") (pintype "passive"))
      (node (ref "RCV_GND") (pin "4") (pinfunction "4_4") (pintype "passive"))
      (node (ref "RCV_GND") (pin "5") (pinfunction "5_5") (pintype "passive"))
      (node (ref "RCV_GND") (pin "6") (pinfunction "6_6") (pintype "passive"))
      (node (ref "RCV_GND") (pin "7") (pinfunction "7_7") (pintype "passive"))
      (node (ref "RCV_GND") (pin "8") (pinfunction "8_8") (pintype "passive"))
      (node (ref "RCV_PPM") (pin "3") (pinfunction "3_3") (pintype "passive"))
      (node (ref "U1") (pin "1") (pinfunction "CLKIN_1") (pintype "bidirectional"))
      (node (ref "U1") (pin "11") (pinfunction "FSYNC_11") (pintype "bidirectional"))
      (node (ref "U1") (pin "18") (pinfunction "GND_18") (pintype "bidirectional"))
      (node (ref "U10") (pin "3") (pinfunction "GND_3") (pintype "bidirectional"))
      (node (ref "U9") (pin "11") (pinfunction "GND_11") (pintype "bidirectional"))
      (node (ref "U9") (pin "9") (pinfunction "GND_9") (pintype "bidirectional"))
      (node (ref "X1") (pin "3") (pinfunction "1_3") (pintype "passive"))
    )
    (net (code "82") (name "Net-(DIO_22-53-Pad6)") (class "Default")
      (node (ref "DIO_22-53") (pin "6") (pinfunction "6_6") (pintype "passive"))
      (node (ref "U$9") (pin "4") (pinfunction "4_4") (pintype "passive"))
    )
    (net (code "83") (name "Net-(DIO_22-53-Pad7)") (class "Default")
      (node (ref "DIO_22-53") (pin "7") (pinfunction "7_7") (pintype "passive"))
      (node (ref "U$8") (pin "14") (pinfunction "14_14") (pintype "passive"))
    )
    (net (code "84") (name "Net-(DIO_22-53-Pad8)") (class "Default")
      (node (ref "DIO_22-53") (pin "8") (pinfunction "8_8") (pintype "passive"))
      (node (ref "U$9") (pin "5") (pinfunction "5_5") (pintype "passive"))
    )
    (net (code "85") (name "Net-(DIO_22-53-Pad9)") (class "Default")
      (node (ref "DIO_22-53") (pin "9") (pinfunction "9_9") (pintype "passive"))
      (node (ref "U$8") (pin "13") (pinfunction "13_13") (pintype "passive"))
    )
    (net (code "86") (name "Net-(DIO_22-53-Pad11)") (class "Default")
      (node (ref "DIO_22-53") (pin "11") (pinfunction "11_11") (pintype "passive"))
      (node (ref "U$8") (pin "12") (pinfunction "12_12") (pintype "passive"))
    )
    (net (code "87") (name "Net-(DIO_22-53-Pad27)") (class "Default")
      (node (ref "DIO_22-53") (pin "27") (pinfunction "27_27") (pintype "passive"))
      (node (ref "U$8") (pin "4") (pinfunction "4_4") (pintype "passive"))
    )
    (net (code "88") (name "Net-(IOREF-Pad1)") (class "Default")
      (node (ref "IOREF") (pin "1") (pinfunction "1_1") (pintype "passive"))
      (node (ref "IOREF") (pin "2") (pinfunction "2_2") (pintype "passive"))
    )
    (net (code "89") (name "Net-(LED1-PadA)") (class "Default")
      (node (ref "LED1") (pin "A") (pinfunction "A_A") (pintype "passive"))
      (node (ref "R9") (pin "1") (pinfunction "1_1") (pintype "passive"))
    )
    (net (code "90") (name "Net-(LED2-PadA)") (class "Default")
      (node (ref "LED2") (pin "A") (pinfunction "A_A") (pintype "passive"))
      (node (ref "R10") (pin "1") (pinfunction "1_1") (pintype "passive"))
    )
    (net (code "91") (name "Net-(LED3-PadA)") (class "Default")
      (node (ref "LED3") (pin "A") (pinfunction "A_A") (pintype "passive"))
      (node (ref "R11") (pin "1") (pinfunction "1_1") (pintype "passive"))
    )
    (net (code "92") (name "Net-(LED4-PadA)") (class "Default")
      (node (ref "LED4") (pin "A") (pinfunction "A_A") (pintype "passive"))
      (node (ref "R12") (pin "1") (pinfunction "1_1") (pintype "passive"))
    )
    (net (code "93") (name "Net-(U1-AUX_CL)") (class "Default")
      (node (ref "EXT_MAG") (pin "4") (pinfunction "4_4") (pintype "passive"))
      (node (ref "U1") (pin "7") (pinfunction "AUX_CL_7") (pintype "bidirectional"))
    )
    (net (code "94") (name "Net-(U1-AUX_DA)") (class "Default")
      (node (ref "EXT_MAG") (pin "3") (pinfunction "3_3") (pintype "passive"))
      (node (ref "U1") (pin "6") (pinfunction "AUX_DA_6") (pintype "bidirectional"))
    )
    (net (code "95") (name "Net-(U1-CPOUT)") (class "Default")
      (node (ref "C4") (pin "1") (pinfunction "1_1") (pintype "passive"))
      (node (ref "U1") (pin "20") (pinfunction "CPOUT_20") (pintype "bidirectional"))
    )
    (net (code "96") (name "Net-(U1-REGOUT)") (class "Default")
      (node (ref "C2") (pin "1") (pinfunction "1_1") (pintype "passive"))
      (node (ref "U1") (pin "10") (pinfunction "REGOUT_10") (pintype "bidirectional"))
    )
    (net (code "97") (name "Net-(U9-C1)") (class "Default")
      (node (ref "C5") (pin "1") (pinfunction "1_1") (pintype "passive"))
      (node (ref "U9") (pin "10") (pinfunction "C1_10") (pintype "bidirectional"))
    )
    (net (code "98") (name "Net-(U9-SETC)") (class "Default")
      (node (ref "C6") (pin "2") (pinfunction "2_2") (pintype "passive"))
      (node (ref "U9") (pin "12") (pinfunction "SETC_12") (pintype "bidirectional"))
    )
    (net (code "99") (name "Net-(U9-SETP)") (class "Default")
      (node (ref "C6") (pin "1") (pinfunction "1_1") (pintype "passive"))
      (node (ref "U9") (pin "8") (pinfunction "SETP_8") (pintype "bidirectional"))
    )
    (net (code "100") (name "Net-(X1E-1)") (class "Default")
      (node (ref "GPSBAT") (pin "2") (pinfunction "2_2") (pintype "passive"))
      (node (ref "X1") (pin "5") (pinfunction "1_5") (pintype "passive"))
    )
    (net (code "101") (name "unconnected-(ADC_HIGH1-Pad1)") (class "Default")
      (node (ref "ADC_HIGH1") (pin "1") (pinfunction "1_1") (pintype "passive"))
    )
    (net (code "102") (name "unconnected-(ADC_HIGH1-Pad2)") (class "Default")
      (node (ref "ADC_HIGH1") (pin "2") (pinfunction "2_2") (pintype "passive"))
    )
    (net (code "103") (name "unconnected-(ADC_HIGH1-Pad3)") (class "Default")
      (node (ref "ADC_HIGH1") (pin "3") (pinfunction "3_3") (pintype "passive"))
    )
    (net (code "104") (name "unconnected-(ADC_HIGH1-Pad4)") (class "Default")
      (node (ref "ADC_HIGH1") (pin "4") (pinfunction "4_4") (pintype "passive"))
    )
    (net (code "105") (name "unconnected-(ADC_HIGH1-Pad5)") (class "Default")
      (node (ref "ADC_HIGH1") (pin "5") (pinfunction "5_5") (pintype "passive"))
    )
    (net (code "106") (name "unconnected-(ADC_HIGH1-Pad6)") (class "Default")
      (node (ref "ADC_HIGH1") (pin "6") (pinfunction "6_6") (pintype "passive"))
    )
    (net (code "107") (name "unconnected-(ADC_HIGH1-Pad7)") (class "Default")
      (node (ref "ADC_HIGH1") (pin "7") (pinfunction "7_7") (pintype "passive"))
    )
    (net (code "108") (name "unconnected-(ADC_HIGH1-Pad8)") (class "Default")
      (node (ref "ADC_HIGH1") (pin "8") (pinfunction "8_8") (pintype "passive"))
    )
    (net (code "109") (name "unconnected-(ADC_HIGH2-Pad1)") (class "Default")
      (node (ref "ADC_HIGH2") (pin "1") (pinfunction "1_1") (pintype "passive"))
    )
    (net (code "110") (name "unconnected-(ADC_HIGH2-Pad2)") (class "Default")
      (node (ref "ADC_HIGH2") (pin "2") (pinfunction "2_2") (pintype "passive"))
    )
    (net (code "111") (name "unconnected-(ADC_HIGH2-Pad3)") (class "Default")
      (node (ref "ADC_HIGH2") (pin "3") (pinfunction "3_3") (pintype "passive"))
    )
    (net (code "112") (name "unconnected-(ADC_HIGH2-Pad4)") (class "Default")
      (node (ref "ADC_HIGH2") (pin "4") (pinfunction "4_4") (pintype "passive"))
    )
    (net (code "113") (name "unconnected-(ADC_HIGH2-Pad5)") (class "Default")
      (node (ref "ADC_HIGH2") (pin "5") (pinfunction "5_5") (pintype "passive"))
    )
    (net (code "114") (name "unconnected-(ADC_HIGH2-Pad6)") (class "Default")
      (node (ref "ADC_HIGH2") (pin "6") (pinfunction "6_6") (pintype "passive"))
    )
    (net (code "115") (name "unconnected-(ADC_HIGH2-Pad7)") (class "Default")
      (node (ref "ADC_HIGH2") (pin "7") (pinfunction "7_7") (pintype "passive"))
    )
    (net (code "116") (name "unconnected-(ADC_HIGH2-Pad8)") (class "Default")
      (node (ref "ADC_HIGH2") (pin "8") (pinfunction "8_8") (pintype "passive"))
    )
    (net (code "117") (name "unconnected-(ESC_PWR-Pad5)") (class "Default")
      (node (ref "ESC_PWR") (pin "5") (pinfunction "5_5") (pintype "passive"))
    )
    (net (code "118") (name "unconnected-(ESC_PWR-Pad6)") (class "Default")
      (node (ref "ESC_PWR") (pin "6") (pinfunction "6_6") (pintype "passive"))
    )
    (net (code "119") (name "unconnected-(ESC_PWR-Pad7)") (class "Default")
      (node (ref "ESC_PWR") (pin "7") (pinfunction "7_7") (pintype "passive"))
    )
    (net (code "120") (name "unconnected-(ESC_PWR-Pad8)") (class "Default")
      (node (ref "ESC_PWR") (pin "8") (pinfunction "8_8") (pintype "passive"))
    )
    (net (code "121") (name "unconnected-(ICSP-Pad1)") (class "Default")
      (node (ref "ICSP") (pin "1") (pinfunction "1_1") (pintype "passive"))
    )
    (net (code "122") (name "unconnected-(ICSP-Pad2)") (class "Default")
      (node (ref "ICSP") (pin "2") (pinfunction "2_2") (pintype "passive"))
    )
    (net (code "123") (name "unconnected-(ICSP-Pad3)") (class "Default")
      (node (ref "ICSP") (pin "3") (pinfunction "3_3") (pintype "passive"))
    )
    (net (code "124") (name "unconnected-(ICSP-Pad4)") (class "Default")
      (node (ref "ICSP") (pin "4") (pinfunction "4_4") (pintype "passive"))
    )
    (net (code "125") (name "unconnected-(ICSP-Pad5)") (class "Default")
      (node (ref "ICSP") (pin "5") (pinfunction "5_5") (pintype "passive"))
    )
    (net (code "126") (name "unconnected-(ICSP-Pad6)") (class "Default")
      (node (ref "ICSP") (pin "6") (pinfunction "6_6") (pintype "passive"))
    )
    (net (code "127") (name "unconnected-(RCV_PWR-Pad2)") (class "Default")
      (node (ref "RCV_PWR") (pin "2") (pinfunction "2_2") (pintype "passive"))
    )
    (net (code "128") (name "unconnected-(RCV_PWR-Pad3)") (class "Default")
      (node (ref "RCV_PWR") (pin "3") (pinfunction "3_3") (pintype "passive"))
    )
    (net (code "129") (name "unconnected-(RCV_PWR-Pad4)") (class "Default")
      (node (ref "RCV_PWR") (pin "4") (pinfunction "4_4") (pintype "passive"))
    )
    (net (code "130") (name "unconnected-(RCV_PWR-Pad5)") (class "Default")
      (node (ref "RCV_PWR") (pin "5") (pinfunction "5_5") (pintype "passive"))
    )
    (net (code "131") (name "unconnected-(RCV_PWR-Pad6)") (class "Default")
      (node (ref "RCV_PWR") (pin "6") (pinfunction "6_6") (pintype "passive"))
    )
    (net (code "132") (name "unconnected-(RCV_PWR-Pad7)") (class "Default")
      (node (ref "RCV_PWR") (pin "7") (pinfunction "7_7") (pintype "passive"))
    )
    (net (code "133") (name "unconnected-(RCV_PWR-Pad8)") (class "Default")
      (node (ref "RCV_PWR") (pin "8") (pinfunction "8_8") (pintype "passive"))
    )
    (net (code "134") (name "unconnected-(U1-NC1-Pad2)") (class "Default")
      (node (ref "U1") (pin "2") (pinfunction "NC1_2") (pintype "bidirectional"))
    )
    (net (code "135") (name "unconnected-(U1-NC2-Pad3)") (class "Default")
      (node (ref "U1") (pin "3") (pinfunction "NC2_3") (pintype "bidirectional"))
    )
    (net (code "136") (name "unconnected-(U1-NC3-Pad4)") (class "Default")
      (node (ref "U1") (pin "4") (pinfunction "NC3_4") (pintype "bidirectional"))
    )
    (net (code "137") (name "unconnected-(U1-NC4-Pad5)") (class "Default")
      (node (ref "U1") (pin "5") (pinfunction "NC4_5") (pintype "bidirectional"))
    )
    (net (code "138") (name "unconnected-(U1-NC5-Pad14)") (class "Default")
      (node (ref "U1") (pin "14") (pinfunction "NC5_14") (pintype "bidirectional"))
    )
    (net (code "139") (name "unconnected-(U1-NC6-Pad15)") (class "Default")
      (node (ref "U1") (pin "15") (pinfunction "NC6_15") (pintype "bidirectional"))
    )
    (net (code "140") (name "unconnected-(U1-NC7-Pad16)") (class "Default")
      (node (ref "U1") (pin "16") (pinfunction "NC7_16") (pintype "bidirectional"))
    )
    (net (code "141") (name "unconnected-(U1-NC8-Pad17)") (class "Default")
      (node (ref "U1") (pin "17") (pinfunction "NC8_17") (pintype "bidirectional"))
    )
    (net (code "142") (name "unconnected-(U1-RESV1-Pad19)") (class "Default")
      (node (ref "U1") (pin "19") (pinfunction "RESV1_19") (pintype "bidirectional"))
    )
    (net (code "143") (name "unconnected-(U1-RESV2-Pad21)") (class "Default")
      (node (ref "U1") (pin "21") (pinfunction "RESV2_21") (pintype "bidirectional"))
    )
    (net (code "144") (name "unconnected-(U9-DRDY-Pad15)") (class "Default")
      (node (ref "U9") (pin "15") (pinfunction "DRDY_15") (pintype "bidirectional"))
    )
    (net (code "145") (name "unconnected-(U9-NC-Pad3)") (class "Default")
      (node (ref "U9") (pin "3") (pinfunction "NC_3") (pintype "bidirectional"))
    )
    (net (code "146") (name "unconnected-(U9-NC-Pad5)") (class "Default")
      (node (ref "U9") (pin "5") (pinfunction "NC_5") (pintype "bidirectional"))
    )
    (net (code "147") (name "unconnected-(U9-NC-Pad6)") (class "Default")
      (node (ref "U9") (pin "6") (pinfunction "NC_6") (pintype "bidirectional"))
    )
    (net (code "148") (name "unconnected-(U9-NC-Pad7)") (class "Default")
      (node (ref "U9") (pin "7") (pinfunction "NC_7") (pintype "bidirectional"))
    )
    (net (code "149") (name "unconnected-(U9-NC-Pad14)") (class "Default")
      (node (ref "U9") (pin "14") (pinfunction "NC_14") (pintype "bidirectional"))
    )
    (net (code "150") (name "unconnected-(U10-SDO-Pad6)") (class "Default")
      (node (ref "U10") (pin "6") (pinfunction "SDO_6") (pintype "bidirectional"))
    )
  )
)
